# Multivibrator.net
KiCad netlist of a schematic drawn in Altium Designer
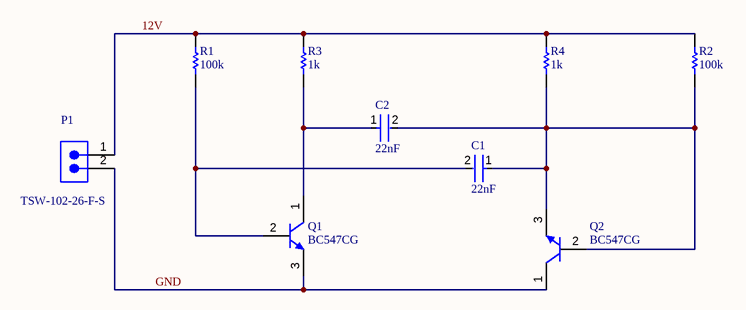
[diagram p0: Multivibrator.SchDoc]

(export (version "E")
  (design (tool "Eeschema 10.0.6"))
  (components
    (comp (ref "C1")
      (value "22nF")
      (footprint "FP-C0603C-CF-IPC_A")
      (fields (field (name "Comment") "Capacitor 22nF +/-5% 16V 0603"))
      (libsource (lib "Georges Lab") (part "b4654b650e69147ec39a6b967a45e02"))
    )
    (comp (ref "C2")
      (value "22nF")
      (footprint "FP-C0603C-CF-IPC_A")
      (fields (field (name "Comment") "Capacitor 22nF +/-5% 16V 0603"))
      (libsource (lib "Georges Lab") (part "b4654b650e69147ec39a6b967a45e02"))
    )
    (comp (ref "P1")
      (value "TSW-102-26-F-S")
      (footprint "SMTC-TSW-102-26-XX-S")
      (libsource (lib "Georges Lab") (part "SMTC-TSW-102-X-X-S-X"))
    )
    (comp (ref "Q1")
      (value "BC547CG")
      (footprint "ONSC-TO-92-3-29-11")
      (description "Small Signal Bipolar Transistor, 0.1A I(C), 45V V(BR)CEO, 1-Element, NPN, Silicon, TO-92")
      (libsource (lib "Georges Lab") (part "ONSC-NPN-C1B2E3-3"))
    )
    (comp (ref "Q2")
      (value "BC547CG")
      (footprint "ONSC-TO-92-3-29-11")
      (description "Small Signal Bipolar Transistor, 0.1A I(C), 45V V(BR)CEO, 1-Element, NPN, Silicon, TO-92")
      (libsource (lib "Georges Lab") (part "ONSC-NPN-C1B2E3-3"))
    )
    (comp (ref "R1")
      (value "100k")
      (footprint "RESC2013X70X40ML20T20")
      (fields
        (field (name "TOLERANCE") "5%")
        (field (name "POWER") "125mW")
        (field (name "Comment") "Resistor 100K +/-5% 0805 125 mW")
      )
      (libsource (lib "Georges Lab") (part "RES"))
    )
    (comp (ref "R2")
      (value "100k")
      (footprint "RESC2013X70X40ML20T20")
      (fields
        (field (name "TOLERANCE") "5%")
        (field (name "POWER") "125mW")
        (field (name "Comment") "Resistor 100K +/-5% 0805 125 mW")
      )
      (libsource (lib "Georges Lab") (part "RES"))
    )
    (comp (ref "R3")
      (value "1k")
      (footprint "RESC2013X70X40ML20T20")
      (fields
        (field (name "POWER") "125mW")
        (field (name "TOLERANCE") "5%")
        (field (name "Comment") "Resistor 1K +/-5% 0805 500 mW")
      )
      (libsource (lib "Georges Lab") (part "RES"))
    )
    (comp (ref "R4")
      (value "1k")
      (footprint "RESC2013X70X40ML20T20")
      (fields
        (field (name "POWER") "125mW")
        (field (name "TOLERANCE") "5%")
        (field (name "Comment") "Resistor 1K +/-5% 0805 500 mW")
      )
      (libsource (lib "Georges Lab") (part "RES"))
    )
  )
  (nets
    (net (code "1") (name "/12V") (class "Default")
      (node (ref "P1") (pin "1") (pinfunction "1_1") (pintype "passive"))
      (node (ref "R1") (pin "2") (pinfunction "2_2") (pintype "passive"))
      (node (ref "R2") (pin "2") (pinfunction "2_2") (pintype "passive"))
      (node (ref "R3") (pin "2") (pinfunction "2_2") (pintype "passive"))
      (node (ref "R4") (pin "2") (pinfunction "2_2") (pintype "passive"))
    )
    (net (code "2") (name "/GND") (class "Default")
      (node (ref "P1") (pin "2") (pinfunction "2_2") (pintype "passive"))
      (node (ref "Q1") (pin "3") (pinfunction "E_3") (pintype "passive"))
      (node (ref "Q2") (pin "1") (pinfunction "C_1") (pintype "passive"))
    )
    (net (code "3") (name "Net-(Q1-B)") (class "Default")
      (node (ref "C1") (pin "2") (pinfunction "2_2") (pintype "passive"))
      (node (ref "Q1") (pin "2") (pinfunction "B_2") (pintype "passive"))
      (node (ref "R1") (pin "1") (pinfunction "1_1") (pintype "passive"))
    )
    (net (code "4") (name "Net-(Q1-C)") (class "Default")
      (node (ref "C2") (pin "1") (pinfunction "1_1") (pintype "passive"))
      (node (ref "Q1") (pin "1") (pinfunction "C_1") (pintype "passive"))
      (node (ref "R3") (pin "1") (pinfunction "1_1") (pintype "passive"))
    )
    (net (code "5") (name "Net-(Q2-B)") (class "Default")
      (node (ref "C1") (pin "1") (pinfunction "1_1") (pintype "passive"))
      (node (ref "C2") (pin "2") (pinfunction "2_2") (pintype "passive"))
      (node (ref "Q2") (pin "2") (pinfunction "B_2") (pintype "passive"))
      (node (ref "Q2") (pin "3") (pinfunction "E_3") (pintype "passive"))
      (node (ref "R2") (pin "1") (pinfunction "1_1") (pintype "passive"))
      (node (ref "R4") (pin "1") (pinfunction "1_1") (pintype "passive"))
    )
  )
)
